# ProPrj_Flight_Radar_Time_Sketch_2026-05-.net
KiCad netlist of a schematic drawn in EasyEDA Pro
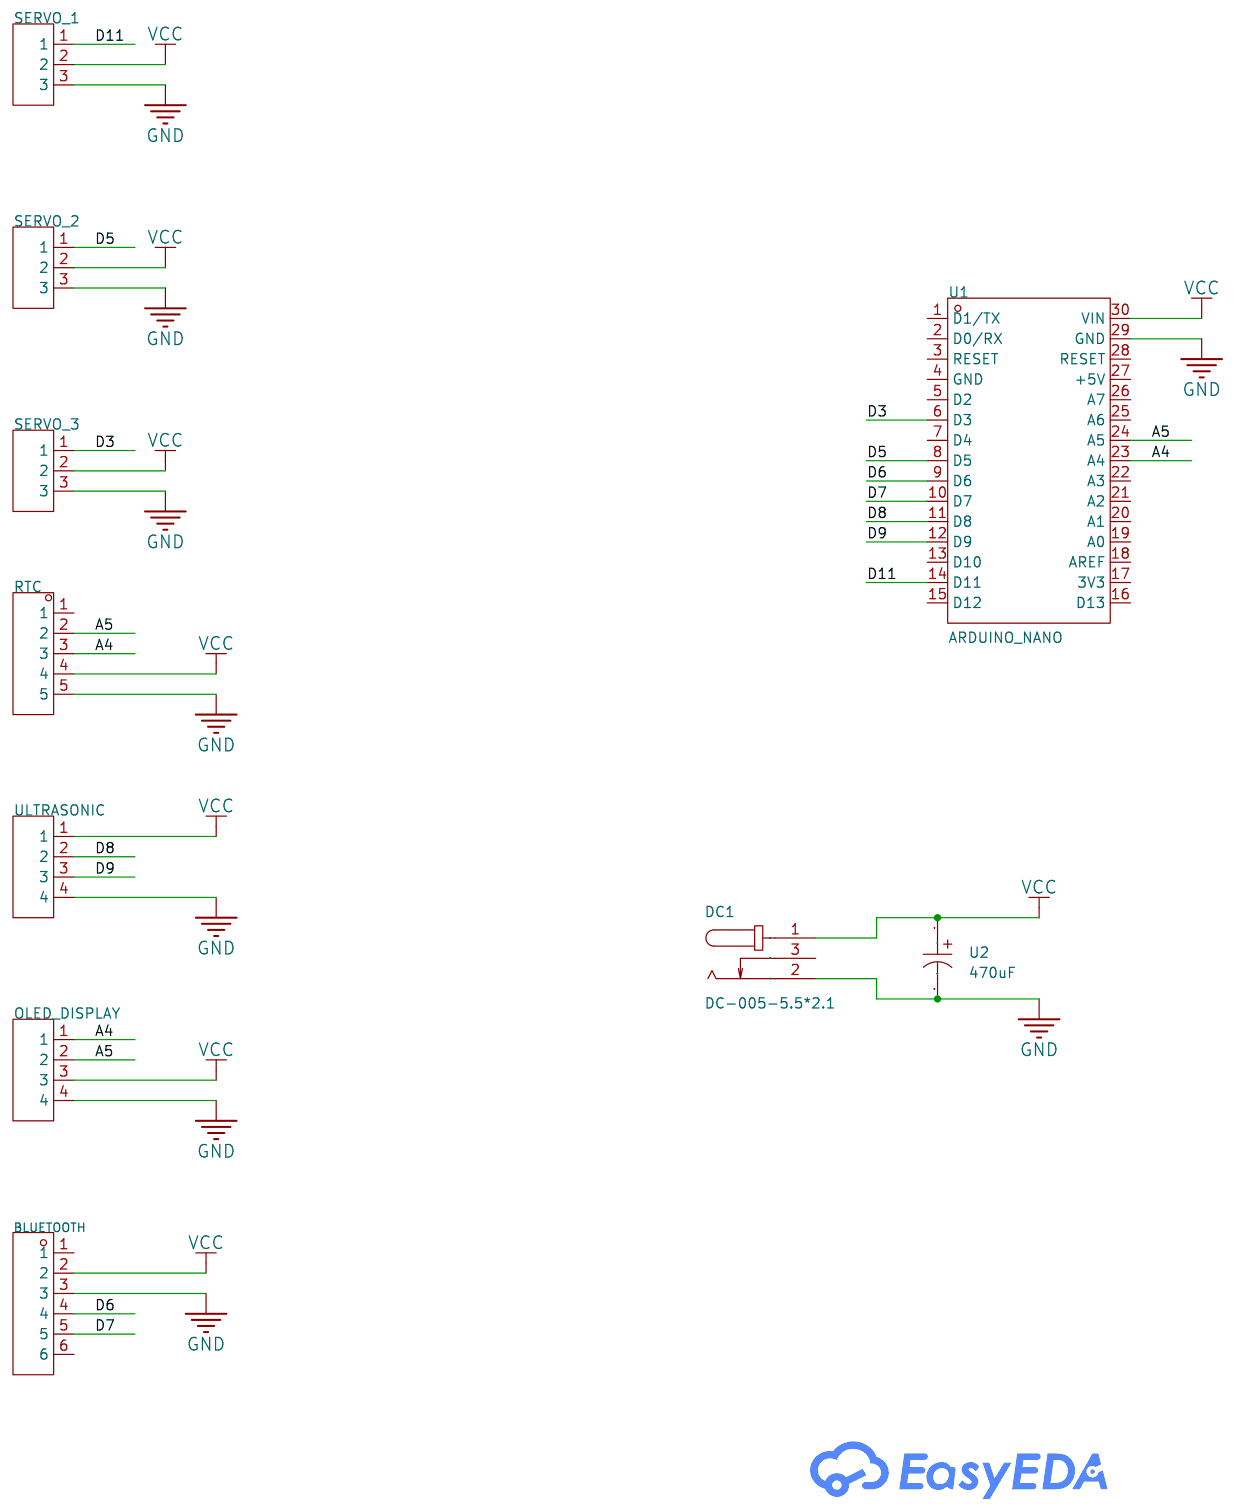
[diagram p0: schematic sheet]

(export (version "E")
  (design (tool "Eeschema 10.0.6"))
  (components
    (comp (ref "BLUETOOTH")
      (value "~")
      (footprint "easyedapro:HDR-TH_6P-P2.54-V-F")
      (libsource (lib "easyedapro") (part "Header-Female-2.54_1x6"))
    )
    (comp (ref "DC1")
      (value "DC-005-5.5*2.1")
      (footprint "easyedapro:DC-IN-TH_DC-005-2")
      (libsource (lib "easyedapro") (part "DC-005-5.5*2.1"))
    )
    (comp (ref "OLED_DISPLAY")
      (value "~")
      (footprint "easyedapro:HDR-TH_4P-P2.54-V-M")
      (libsource (lib "easyedapro") (part "PZ254V-11-04P"))
    )
    (comp (ref "RTC")
      (value "~")
      (footprint "easyedapro:HDR-TH_5P-P2.54-V-M")
      (libsource (lib "easyedapro") (part "MTP125-1105S1"))
    )
    (comp (ref "SERVO_1")
      (value "~")
      (footprint "easyedapro:HDR-TH_3P-P2.54-V-M")
      (libsource (lib "easyedapro") (part "PZ254V-11-03P_C2937625"))
    )
    (comp (ref "SERVO_2")
      (value "~")
      (footprint "easyedapro:HDR-TH_3P-P2.54-V-M")
      (libsource (lib "easyedapro") (part "PZ254V-11-03P_C2937625"))
    )
    (comp (ref "SERVO_3")
      (value "~")
      (footprint "easyedapro:HDR-TH_3P-P2.54-V-M")
      (libsource (lib "easyedapro") (part "PZ254V-11-03P_C2937625"))
    )
    (comp (ref "U1")
      (value "ARDUINO_NANO")
      (footprint "easyedapro:COMM-TH_ARDUINO_NANO")
      (libsource (lib "easyedapro") (part "ARDUINO_NANO"))
    )
    (comp (ref "U2")
      (value "470uF")
      (footprint "easyedapro:CAP-TH_BD6.3-P2.50-D1.0-FD")
      (fields (field (name "Manufacturer Part") "RS471M160E100R1Z00ZZ") (field (name "Manufacturer") "创慧电子"))
      (libsource (lib "easyedapro") (part "RS471M160E100R1Z00ZZ"))
    )
    (comp (ref "ULTRASONIC")
      (value "~")
      (footprint "easyedapro:HDR-TH_4P-P2.54-V-M")
      (libsource (lib "easyedapro") (part "PZ254V-11-04P"))
    )
  )
  (nets
    (net (code "1") (name "/A4") (class "Default")
      (node (ref "OLED_DISPLAY") (pin "1") (pinfunction "1_1") (pintype "unspecified"))
      (node (ref "RTC") (pin "3") (pinfunction "3_3") (pintype "input"))
      (node (ref "U1") (pin "23") (pinfunction "A4_23") (pintype "unspecified"))
    )
    (net (code "2") (name "/A5") (class "Default")
      (node (ref "OLED_DISPLAY") (pin "2") (pinfunction "2_2") (pintype "unspecified"))
      (node (ref "RTC") (pin "2") (pinfunction "2_2") (pintype "input"))
      (node (ref "U1") (pin "24") (pinfunction "A5_24") (pintype "unspecified"))
    )
    (net (code "3") (name "/D3") (class "Default")
      (node (ref "SERVO_3") (pin "1") (pinfunction "1_1") (pintype "unspecified"))
      (node (ref "U1") (pin "6") (pinfunction "D3_6") (pintype "unspecified"))
    )
    (net (code "4") (name "/D5") (class "Default")
      (node (ref "SERVO_2") (pin "1") (pinfunction "1_1") (pintype "unspecified"))
      (node (ref "U1") (pin "8") (pinfunction "D5_8") (pintype "unspecified"))
    )
    (net (code "5") (name "/D6") (class "Default")
      (node (ref "BLUETOOTH") (pin "4") (pinfunction "4_4") (pintype "input"))
      (node (ref "U1") (pin "9") (pinfunction "D6_9") (pintype "unspecified"))
    )
    (net (code "6") (name "/D7") (class "Default")
      (node (ref "BLUETOOTH") (pin "5") (pinfunction "5_5") (pintype "input"))
      (node (ref "U1") (pin "10") (pinfunction "D7_10") (pintype "unspecified"))
    )
    (net (code "7") (name "/D8") (class "Default")
      (node (ref "U1") (pin "11") (pinfunction "D8_11") (pintype "unspecified"))
      (node (ref "ULTRASONIC") (pin "2") (pinfunction "2_2") (pintype "unspecified"))
    )
    (net (code "8") (name "/D9") (class "Default")
      (node (ref "U1") (pin "12") (pinfunction "D9_12") (pintype "unspecified"))
      (node (ref "ULTRASONIC") (pin "3") (pinfunction "3_3") (pintype "unspecified"))
    )
    (net (code "9") (name "/D11") (class "Default")
      (node (ref "SERVO_1") (pin "1") (pinfunction "1_1") (pintype "unspecified"))
      (node (ref "U1") (pin "14") (pinfunction "D11_14") (pintype "unspecified"))
    )
    (net (code "10") (name "GND") (class "Default")
      (node (ref "BLUETOOTH") (pin "3") (pinfunction "3_3") (pintype "input"))
      (node (ref "DC1") (pin "2") (pinfunction "2_2") (pintype "unspecified"))
      (node (ref "OLED_DISPLAY") (pin "4") (pinfunction "4_4") (pintype "unspecified"))
      (node (ref "RTC") (pin "5") (pinfunction "5_5") (pintype "input"))
      (node (ref "SERVO_1") (pin "3") (pinfunction "3_3") (pintype "unspecified"))
      (node (ref "SERVO_2") (pin "3") (pinfunction "3_3") (pintype "unspecified"))
      (node (ref "SERVO_3") (pin "3") (pinfunction "3_3") (pintype "unspecified"))
      (node (ref "U1") (pin "29") (pinfunction "GND_29") (pintype "unspecified"))
      (node (ref "U2") (pin "2") (pinfunction "2_2") (pintype "input"))
      (node (ref "ULTRASONIC") (pin "4") (pinfunction "4_4") (pintype "unspecified"))
    )
    (net (code "11") (name "VCC") (class "Default")
      (node (ref "BLUETOOTH") (pin "2") (pinfunction "2_2") (pintype "input"))
      (node (ref "DC1") (pin "1") (pinfunction "1_1") (pintype "unspecified"))
      (node (ref "OLED_DISPLAY") (pin "3") (pinfunction "3_3") (pintype "unspecified"))
      (node (ref "RTC") (pin "4") (pinfunction "4_4") (pintype "input"))
      (node (ref "SERVO_1") (pin "2") (pinfunction "2_2") (pintype "unspecified"))
      (node (ref "SERVO_2") (pin "2") (pinfunction "2_2") (pintype "unspecified"))
      (node (ref "SERVO_3") (pin "2") (pinfunction "2_2") (pintype "unspecified"))
      (node (ref "U1") (pin "30") (pinfunction "VIN_30") (pintype "unspecified"))
      (node (ref "U2") (pin "1") (pinfunction "1_1") (pintype "input"))
      (node (ref "ULTRASONIC") (pin "1") (pinfunction "1_1") (pintype "unspecified"))
    )
    (net (code "12") (name "unconnected-(BLUETOOTH-Pad1)") (class "Default")
      (node (ref "BLUETOOTH") (pin "1") (pinfunction "1_1") (pintype "input"))
    )
    (net (code "13") (name "unconnected-(BLUETOOTH-Pad6)") (class "Default")
      (node (ref "BLUETOOTH") (pin "6") (pinfunction "6_6") (pintype "input"))
    )
    (net (code "14") (name "unconnected-(DC1-Pad3)") (class "Default")
      (node (ref "DC1") (pin "3") (pinfunction "3_3") (pintype "unspecified"))
    )
    (net (code "15") (name "unconnected-(RTC-Pad1)") (class "Default")
      (node (ref "RTC") (pin "1") (pinfunction "1_1") (pintype "input"))
    )
    (net (code "16") (name "unconnected-(U1-+5V-Pad27)") (class "Default")
      (node (ref "U1") (pin "27") (pinfunction "+5V_27") (pintype "unspecified"))
    )
    (net (code "17") (name "unconnected-(U1-3V3-Pad17)") (class "Default")
      (node (ref "U1") (pin "17") (pinfunction "3V3_17") (pintype "unspecified"))
    )
    (net (code "18") (name "unconnected-(U1-A0-Pad19)") (class "Default")
      (node (ref "U1") (pin "19") (pinfunction "A0_19") (pintype "unspecified"))
    )
    (net (code "19") (name "unconnected-(U1-A1-Pad20)") (class "Default")
      (node (ref "U1") (pin "20") (pinfunction "A1_20") (pintype "unspecified"))
    )
    (net (code "20") (name "unconnected-(U1-A2-Pad21)") (class "Default")
      (node (ref "U1") (pin "21") (pinfunction "A2_21") (pintype "unspecified"))
    )
    (net (code "21") (name "unconnected-(U1-A3-Pad22)") (class "Default")
      (node (ref "U1") (pin "22") (pinfunction "A3_22") (pintype "unspecified"))
    )
    (net (code "22") (name "unconnected-(U1-A6-Pad25)") (class "Default")
      (node (ref "U1") (pin "25") (pinfunction "A6_25") (pintype "unspecified"))
    )
    (net (code "23") (name "unconnected-(U1-A7-Pad26)") (class "Default")
      (node (ref "U1") (pin "26") (pinfunction "A7_26") (pintype "unspecified"))
    )
    (net (code "24") (name "unconnected-(U1-AREF-Pad18)") (class "Default")
      (node (ref "U1") (pin "18") (pinfunction "AREF_18") (pintype "unspecified"))
    )
    (net (code "25") (name "unconnected-(U1-D0{slash}RX-Pad2)") (class "Default")
      (node (ref "U1") (pin "2") (pinfunction "D0/RX_2") (pintype "unspecified"))
    )
    (net (code "26") (name "unconnected-(U1-D1{slash}TX-Pad1)") (class "Default")
      (node (ref "U1") (pin "1") (pinfunction "D1/TX_1") (pintype "unspecified"))
    )
    (net (code "27") (name "unconnected-(U1-D2-Pad5)") (class "Default")
      (node (ref "U1") (pin "5") (pinfunction "D2_5") (pintype "unspecified"))
    )
    (net (code "28") (name "unconnected-(U1-D4-Pad7)") (class "Default")
      (node (ref "U1") (pin "7") (pinfunction "D4_7") (pintype "unspecified"))
    )
    (net (code "29") (name "unconnected-(U1-D10-Pad13)") (class "Default")
      (node (ref "U1") (pin "13") (pinfunction "D10_13") (pintype "unspecified"))
    )
    (net (code "30") (name "unconnected-(U1-D12-Pad15)") (class "Default")
      (node (ref "U1") (pin "15") (pinfunction "D12_15") (pintype "unspecified"))
    )
    (net (code "31") (name "unconnected-(U1-D13-Pad16)") (class "Default")
      (node (ref "U1") (pin "16") (pinfunction "D13_16") (pintype "unspecified"))
    )
    (net (code "32") (name "unconnected-(U1-GND-Pad4)") (class "Default")
      (node (ref "U1") (pin "4") (pinfunction "GND_4") (pintype "unspecified"))
    )
    (net (code "33") (name "unconnected-(U1-RESET-Pad3)") (class "Default")
      (node (ref "U1") (pin "3") (pinfunction "RESET_3") (pintype "unspecified"))
    )
    (net (code "34") (name "unconnected-(U1-RESET-Pad28)") (class "Default")
      (node (ref "U1") (pin "28") (pinfunction "RESET_28") (pintype "unspecified"))
    )
  )
)
